# dualScaleBoard_HX711.net
KiCad netlist of a schematic drawn in EAGLE
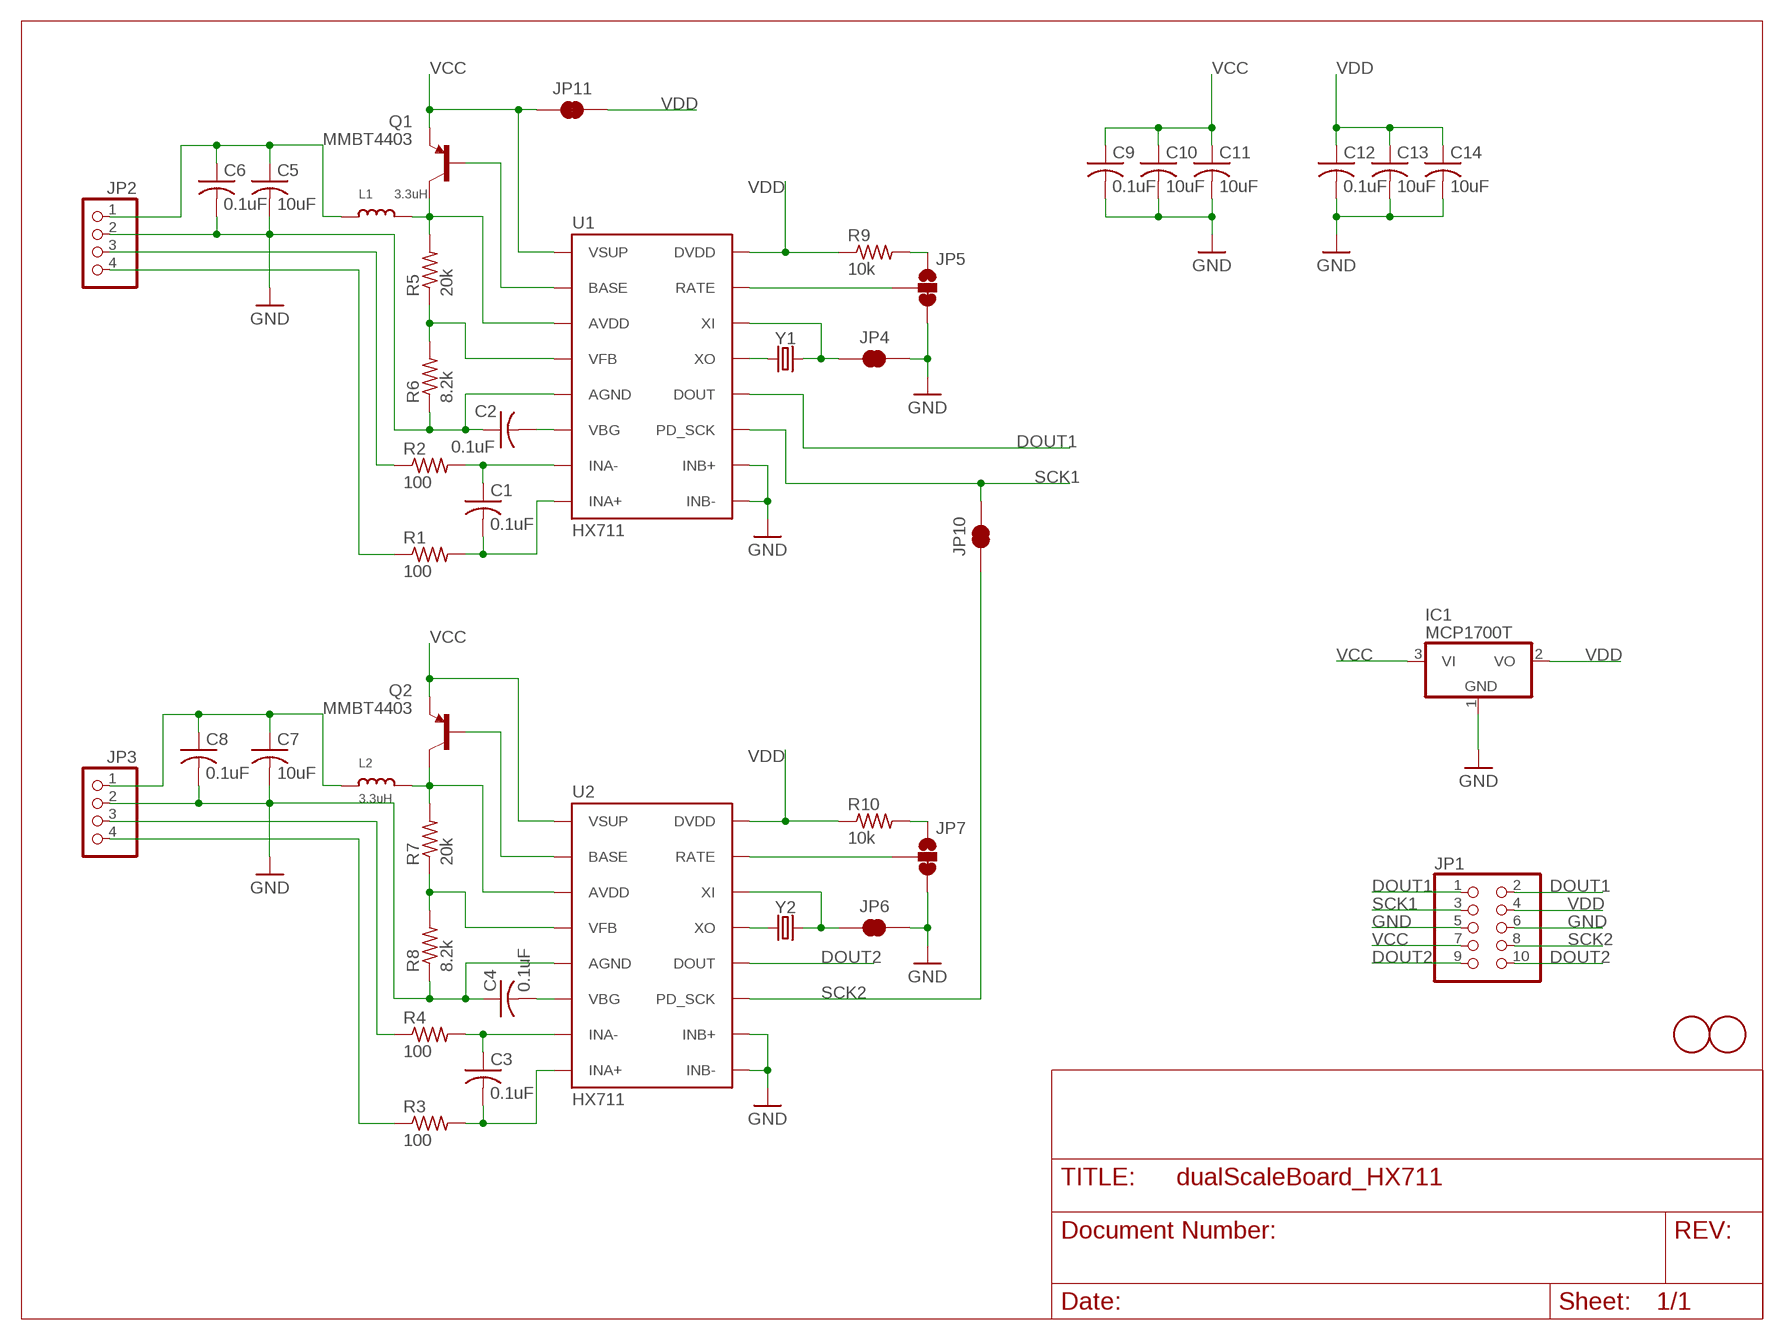
[diagram p0: schematic, sheet 1]

(export (version "E")
  (design (tool "Eeschema 10.0.6"))
  (components
    (comp (ref "C1")
      (value "0.1uF")
      (footprint "eagle-import:C0603")
      (libsource (lib "eagle-import") (part "C-USC0603"))
    )
    (comp (ref "C2")
      (value "0.1uF")
      (footprint "eagle-import:C0603")
      (libsource (lib "eagle-import") (part "C-USC0603"))
    )
    (comp (ref "C3")
      (value "0.1uF")
      (footprint "eagle-import:C0603")
      (libsource (lib "eagle-import") (part "C-USC0603"))
    )
    (comp (ref "C4")
      (value "0.1uF")
      (footprint "eagle-import:C0603")
      (libsource (lib "eagle-import") (part "C-USC0603"))
    )
    (comp (ref "C5")
      (value "10uF")
      (footprint "eagle-import:C0603")
      (libsource (lib "eagle-import") (part "C-USC0603"))
    )
    (comp (ref "C6")
      (value "0.1uF")
      (footprint "eagle-import:C0603")
      (libsource (lib "eagle-import") (part "C-USC0603"))
    )
    (comp (ref "C7")
      (value "10uF")
      (footprint "eagle-import:C0603")
      (libsource (lib "eagle-import") (part "C-USC0603"))
    )
    (comp (ref "C8")
      (value "0.1uF")
      (footprint "eagle-import:C0603")
      (libsource (lib "eagle-import") (part "C-USC0603"))
    )
    (comp (ref "C9")
      (value "0.1uF")
      (footprint "eagle-import:C0603")
      (libsource (lib "eagle-import") (part "C-USC0603"))
    )
    (comp (ref "C10")
      (value "10uF")
      (footprint "eagle-import:C0603")
      (libsource (lib "eagle-import") (part "C-USC0603"))
    )
    (comp (ref "C11")
      (value "10uF")
      (footprint "eagle-import:C0603")
      (libsource (lib "eagle-import") (part "C-USC0603"))
    )
    (comp (ref "C12")
      (value "0.1uF")
      (footprint "eagle-import:C0603")
      (libsource (lib "eagle-import") (part "C-USC0603"))
    )
    (comp (ref "C13")
      (value "10uF")
      (footprint "eagle-import:C0603")
      (libsource (lib "eagle-import") (part "C-USC0603"))
    )
    (comp (ref "C14")
      (value "10uF")
      (footprint "eagle-import:C0603")
      (libsource (lib "eagle-import") (part "C-USC0603"))
    )
    (comp (ref "IC1")
      (value "MCP1700T")
      (footprint "eagle-import:SOT23")
      (libsource (lib "eagle-import") (part "MCP1703CB"))
    )
    (comp (ref "JP1")
      (value "PINHD-2X5")
      (footprint "eagle-import:2X05")
      (libsource (lib "eagle-import") (part "PINHD-2X5"))
    )
    (comp (ref "JP2")
      (value "PINHD-1X4")
      (footprint "eagle-import:1X04")
      (libsource (lib "eagle-import") (part "PINHD-1X4"))
    )
    (comp (ref "JP3")
      (value "PINHD-1X4")
      (footprint "eagle-import:1X04")
      (libsource (lib "eagle-import") (part "PINHD-1X4"))
    )
    (comp (ref "JP4")
      (value "JUMPER-SMT_2_NC_TRACE_SILK")
      (footprint "eagle-import:SMT-JUMPER_2_NC_TRACE_SILK")
      (libsource (lib "eagle-import") (part "JUMPER-SMT_2_NC_TRACE_SILK"))
    )
    (comp (ref "JP5")
      (value "JUMPER-SMT_3_1-NC_TRACE_SILK")
      (footprint "eagle-import:SMT-JUMPER_3_1-NC_TRACE_SILK")
      (libsource (lib "eagle-import") (part "JUMPER-SMT_3_1-NC_TRACE_SILK"))
    )
    (comp (ref "JP6")
      (value "JUMPER-SMT_2_NC_TRACE_SILK")
      (footprint "eagle-import:SMT-JUMPER_2_NC_TRACE_SILK")
      (libsource (lib "eagle-import") (part "JUMPER-SMT_2_NC_TRACE_SILK"))
    )
    (comp (ref "JP7")
      (value "JUMPER-SMT_3_1-NC_TRACE_SILK")
      (footprint "eagle-import:SMT-JUMPER_3_1-NC_TRACE_SILK")
      (libsource (lib "eagle-import") (part "JUMPER-SMT_3_1-NC_TRACE_SILK"))
    )
    (comp (ref "JP10")
      (value "JUMPER-SMT_2_NC_TRACE_SILK")
      (footprint "eagle-import:SMT-JUMPER_2_NC_TRACE_SILK")
      (libsource (lib "eagle-import") (part "JUMPER-SMT_2_NC_TRACE_SILK"))
    )
    (comp (ref "JP11")
      (value "JUMPER-SMT_2_NC_TRACE_SILK")
      (footprint "eagle-import:SMT-JUMPER_2_NC_TRACE_SILK")
      (libsource (lib "eagle-import") (part "JUMPER-SMT_2_NC_TRACE_SILK"))
    )
    (comp (ref "L1")
      (value "3.3uH")
      (footprint "eagle-import:_0603")
      (libsource (lib "eagle-import") (part "INDUCTOR_0603"))
    )
    (comp (ref "L2")
      (value "3.3uH")
      (footprint "eagle-import:_0603")
      (libsource (lib "eagle-import") (part "INDUCTOR_0603"))
    )
    (comp (ref "Q1")
      (value "MMBT4403")
      (footprint "eagle-import:SOT23-3")
      (libsource (lib "eagle-import") (part "TRANSISTOR_PNPMMBT4403"))
    )
    (comp (ref "Q2")
      (value "MMBT4403")
      (footprint "eagle-import:SOT23-3")
      (libsource (lib "eagle-import") (part "TRANSISTOR_PNPMMBT4403"))
    )
    (comp (ref "R1")
      (value "100")
      (footprint "eagle-import:R0402")
      (libsource (lib "eagle-import") (part "R-US_R0402"))
    )
    (comp (ref "R2")
      (value "100")
      (footprint "eagle-import:R0402")
      (libsource (lib "eagle-import") (part "R-US_R0402"))
    )
    (comp (ref "R3")
      (value "100")
      (footprint "eagle-import:R0402")
      (libsource (lib "eagle-import") (part "R-US_R0402"))
    )
    (comp (ref "R4")
      (value "100")
      (footprint "eagle-import:R0402")
      (libsource (lib "eagle-import") (part "R-US_R0402"))
    )
    (comp (ref "R5")
      (value "20k")
      (footprint "eagle-import:R0402")
      (libsource (lib "eagle-import") (part "R-US_R0402"))
    )
    (comp (ref "R6")
      (value "8.2k")
      (footprint "eagle-import:R0402")
      (libsource (lib "eagle-import") (part "R-US_R0402"))
    )
    (comp (ref "R7")
      (value "20k")
      (footprint "eagle-import:R0402")
      (libsource (lib "eagle-import") (part "R-US_R0402"))
    )
    (comp (ref "R8")
      (value "8.2k")
      (footprint "eagle-import:R0402")
      (libsource (lib "eagle-import") (part "R-US_R0402"))
    )
    (comp (ref "R9")
      (value "10k")
      (footprint "eagle-import:R0402")
      (libsource (lib "eagle-import") (part "R-US_R0402"))
    )
    (comp (ref "R10")
      (value "10k")
      (footprint "eagle-import:R0402")
      (libsource (lib "eagle-import") (part "R-US_R0402"))
    )
    (comp (ref "U$1")
      (value "FIDUCIAL")
      (footprint "eagle-import:FIDUCIAL_1MM")
      (libsource (lib "eagle-import") (part "FIDUCIAL"))
    )
    (comp (ref "U$2")
      (value "FIDUCIAL")
      (footprint "eagle-import:FIDUCIAL_1MM")
      (libsource (lib "eagle-import") (part "FIDUCIAL"))
    )
    (comp (ref "U1")
      (value "HX711")
      (footprint "eagle-import:SO16")
      (libsource (lib "eagle-import") (part "HX711"))
    )
    (comp (ref "U2")
      (value "HX711")
      (footprint "eagle-import:SO16")
      (libsource (lib "eagle-import") (part "HX711"))
    )
    (comp (ref "Y1")
      (value "CRYSTALSMD-5X3.2-4PAD")
      (footprint "eagle-import:CRYSTAL-SMD-5X3.2-4PAD")
      (libsource (lib "eagle-import") (part "CRYSTALSMD-5X3.2-4PAD"))
    )
    (comp (ref "Y2")
      (value "CRYSTALSMD-5X3.2-4PAD")
      (footprint "eagle-import:CRYSTAL-SMD-5X3.2-4PAD")
      (libsource (lib "eagle-import") (part "CRYSTALSMD-5X3.2-4PAD"))
    )
  )
  (nets
    (net (code "1") (name "/DOUT1") (class "Default")
      (node (ref "JP1") (pin "1") (pinfunction "1_1") (pintype "passive"))
      (node (ref "JP1") (pin "2") (pinfunction "2_2") (pintype "passive"))
      (node (ref "U1") (pin "12") (pinfunction "DOUT_12") (pintype "bidirectional"))
    )
    (net (code "2") (name "/DOUT2") (class "Default")
      (node (ref "JP1") (pin "10") (pinfunction "10_10") (pintype "passive"))
      (node (ref "JP1") (pin "9") (pinfunction "9_9") (pintype "passive"))
      (node (ref "U2") (pin "12") (pinfunction "DOUT_12") (pintype "bidirectional"))
    )
    (net (code "3") (name "/SCK1") (class "Default")
      (node (ref "JP1") (pin "3") (pinfunction "3_3") (pintype "passive"))
      (node (ref "JP10") (pin "2") (pinfunction "2_2") (pintype "passive"))
      (node (ref "U1") (pin "11") (pinfunction "PD_SCK_11") (pintype "bidirectional"))
    )
    (net (code "4") (name "/SCK2") (class "Default")
      (node (ref "JP1") (pin "8") (pinfunction "8_8") (pintype "passive"))
      (node (ref "JP10") (pin "1") (pinfunction "1_1") (pintype "passive"))
      (node (ref "U2") (pin "11") (pinfunction "PD_SCK_11") (pintype "bidirectional"))
    )
    (net (code "5") (name "/VCC") (class "Default")
      (node (ref "C10") (pin "1") (pinfunction "1_1") (pintype "passive"))
      (node (ref "C11") (pin "1") (pinfunction "1_1") (pintype "passive"))
      (node (ref "C9") (pin "1") (pinfunction "1_1") (pintype "passive"))
      (node (ref "IC1") (pin "3") (pinfunction "VI_3") (pintype "input"))
      (node (ref "JP1") (pin "7") (pinfunction "7_7") (pintype "passive"))
      (node (ref "JP11") (pin "1") (pinfunction "1_1") (pintype "passive"))
      (node (ref "Q1") (pin "2") (pinfunction "E_2") (pintype "passive"))
      (node (ref "Q2") (pin "2") (pinfunction "E_2") (pintype "passive"))
      (node (ref "U1") (pin "1") (pinfunction "VSUP_1") (pintype "bidirectional"))
      (node (ref "U2") (pin "1") (pinfunction "VSUP_1") (pintype "bidirectional"))
    )
    (net (code "6") (name "/VDD") (class "Default")
      (node (ref "C12") (pin "1") (pinfunction "1_1") (pintype "passive"))
      (node (ref "C13") (pin "1") (pinfunction "1_1") (pintype "passive"))
      (node (ref "C14") (pin "1") (pinfunction "1_1") (pintype "passive"))
      (node (ref "IC1") (pin "2") (pinfunction "VO_2") (pintype "passive"))
      (node (ref "JP1") (pin "4") (pinfunction "4_4") (pintype "passive"))
      (node (ref "JP11") (pin "2") (pinfunction "2_2") (pintype "passive"))
      (node (ref "R10") (pin "1") (pinfunction "1_1") (pintype "passive"))
      (node (ref "R9") (pin "1") (pinfunction "1_1") (pintype "passive"))
      (node (ref "U1") (pin "16") (pinfunction "DVDD_16") (pintype "bidirectional"))
      (node (ref "U2") (pin "16") (pinfunction "DVDD_16") (pintype "bidirectional"))
    )
    (net (code "7") (name "GND") (class "Default")
      (node (ref "C10") (pin "2") (pinfunction "2_2") (pintype "passive"))
      (node (ref "C11") (pin "2") (pinfunction "2_2") (pintype "passive"))
      (node (ref "C12") (pin "2") (pinfunction "2_2") (pintype "passive"))
      (node (ref "C13") (pin "2") (pinfunction "2_2") (pintype "passive"))
      (node (ref "C14") (pin "2") (pinfunction "2_2") (pintype "passive"))
      (node (ref "C2") (pin "1") (pinfunction "1_1") (pintype "passive"))
      (node (ref "C4") (pin "1") (pinfunction "1_1") (pintype "passive"))
      (node (ref "C5") (pin "2") (pinfunction "2_2") (pintype "passive"))
      (node (ref "C6") (pin "2") (pinfunction "2_2") (pintype "passive"))
      (node (ref "C7") (pin "2") (pinfunction "2_2") (pintype "passive"))
      (node (ref "C8") (pin "2") (pinfunction "2_2") (pintype "passive"))
      (node (ref "C9") (pin "2") (pinfunction "2_2") (pintype "passive"))
      (node (ref "IC1") (pin "1") (pinfunction "GND_1") (pintype "passive"))
      (node (ref "JP1") (pin "5") (pinfunction "5_5") (pintype "passive"))
      (node (ref "JP1") (pin "6") (pinfunction "6_6") (pintype "passive"))
      (node (ref "JP2") (pin "2") (pinfunction "2_2") (pintype "passive"))
      (node (ref "JP3") (pin "2") (pinfunction "2_2") (pintype "passive"))
      (node (ref "JP4") (pin "2") (pinfunction "2_2") (pintype "passive"))
      (node (ref "JP5") (pin "3") (pinfunction "3_3") (pintype "passive"))
      (node (ref "JP6") (pin "2") (pinfunction "2_2") (pintype "passive"))
      (node (ref "JP7") (pin "3") (pinfunction "3_3") (pintype "passive"))
      (node (ref "R6") (pin "1") (pinfunction "1_1") (pintype "passive"))
      (node (ref "R8") (pin "1") (pinfunction "1_1") (pintype "passive"))
      (node (ref "U1") (pin "10") (pinfunction "INB+_10") (pintype "bidirectional"))
      (node (ref "U1") (pin "5") (pinfunction "AGND_5") (pintype "bidirectional"))
      (node (ref "U1") (pin "9") (pinfunction "INB-_9") (pintype "bidirectional"))
      (node (ref "U2") (pin "10") (pinfunction "INB+_10") (pintype "bidirectional"))
      (node (ref "U2") (pin "5") (pinfunction "AGND_5") (pintype "bidirectional"))
      (node (ref "U2") (pin "9") (pinfunction "INB-_9") (pintype "bidirectional"))
    )
    (net (code "8") (name "Net-(C5-Pad1)") (class "Default")
      (node (ref "C5") (pin "1") (pinfunction "1_1") (pintype "passive"))
      (node (ref "C6") (pin "1") (pinfunction "1_1") (pintype "passive"))
      (node (ref "JP2") (pin "1") (pinfunction "1_1") (pintype "passive"))
      (node (ref "L1") (pin "1") (pinfunction "1_1") (pintype "passive"))
    )
    (net (code "9") (name "Net-(C7-Pad1)") (class "Default")
      (node (ref "C7") (pin "1") (pinfunction "1_1") (pintype "passive"))
      (node (ref "C8") (pin "1") (pinfunction "1_1") (pintype "passive"))
      (node (ref "JP3") (pin "1") (pinfunction "1_1") (pintype "passive"))
      (node (ref "L2") (pin "1") (pinfunction "1_1") (pintype "passive"))
    )
    (net (code "10") (name "Net-(JP2-Pad3)") (class "Default")
      (node (ref "JP2") (pin "3") (pinfunction "3_3") (pintype "passive"))
      (node (ref "R2") (pin "1") (pinfunction "1_1") (pintype "passive"))
    )
    (net (code "11") (name "Net-(JP2-Pad4)") (class "Default")
      (node (ref "JP2") (pin "4") (pinfunction "4_4") (pintype "passive"))
      (node (ref "R1") (pin "1") (pinfunction "1_1") (pintype "passive"))
    )
    (net (code "12") (name "Net-(JP3-Pad3)") (class "Default")
      (node (ref "JP3") (pin "3") (pinfunction "3_3") (pintype "passive"))
      (node (ref "R4") (pin "1") (pinfunction "1_1") (pintype "passive"))
    )
    (net (code "13") (name "Net-(JP3-Pad4)") (class "Default")
      (node (ref "JP3") (pin "4") (pinfunction "4_4") (pintype "passive"))
      (node (ref "R3") (pin "1") (pinfunction "1_1") (pintype "passive"))
    )
    (net (code "14") (name "Net-(JP5-Pad1)") (class "Default")
      (node (ref "JP5") (pin "1") (pinfunction "1_1") (pintype "passive"))
      (node (ref "R9") (pin "2") (pinfunction "2_2") (pintype "passive"))
    )
    (net (code "15") (name "Net-(JP7-Pad1)") (class "Default")
      (node (ref "JP7") (pin "1") (pinfunction "1_1") (pintype "passive"))
      (node (ref "R10") (pin "2") (pinfunction "2_2") (pintype "passive"))
    )
    (net (code "16") (name "Net-(Q1-B)") (class "Default")
      (node (ref "Q1") (pin "1") (pinfunction "B_1") (pintype "passive"))
      (node (ref "U1") (pin "2") (pinfunction "BASE_2") (pintype "bidirectional"))
    )
    (net (code "17") (name "Net-(Q1-C)") (class "Default")
      (node (ref "L1") (pin "2") (pinfunction "2_2") (pintype "passive"))
      (node (ref "Q1") (pin "3") (pinfunction "C_3") (pintype "passive"))
      (node (ref "R5") (pin "2") (pinfunction "2_2") (pintype "passive"))
      (node (ref "U1") (pin "3") (pinfunction "AVDD_3") (pintype "bidirectional"))
    )
    (net (code "18") (name "Net-(Q2-B)") (class "Default")
      (node (ref "Q2") (pin "1") (pinfunction "B_1") (pintype "passive"))
      (node (ref "U2") (pin "2") (pinfunction "BASE_2") (pintype "bidirectional"))
    )
    (net (code "19") (name "Net-(Q2-C)") (class "Default")
      (node (ref "L2") (pin "2") (pinfunction "2_2") (pintype "passive"))
      (node (ref "Q2") (pin "3") (pinfunction "C_3") (pintype "passive"))
      (node (ref "R7") (pin "2") (pinfunction "2_2") (pintype "passive"))
      (node (ref "U2") (pin "3") (pinfunction "AVDD_3") (pintype "bidirectional"))
    )
    (net (code "20") (name "Net-(U1-INA+)") (class "Default")
      (node (ref "C1") (pin "2") (pinfunction "2_2") (pintype "passive"))
      (node (ref "R1") (pin "2") (pinfunction "2_2") (pintype "passive"))
      (node (ref "U1") (pin "8") (pinfunction "INA+_8") (pintype "bidirectional"))
    )
    (net (code "21") (name "Net-(U1-INA-)") (class "Default")
      (node (ref "C1") (pin "1") (pinfunction "1_1") (pintype "passive"))
      (node (ref "R2") (pin "2") (pinfunction "2_2") (pintype "passive"))
      (node (ref "U1") (pin "7") (pinfunction "INA-_7") (pintype "bidirectional"))
    )
    (net (code "22") (name "Net-(U1-RATE)") (class "Default")
      (node (ref "JP5") (pin "2") (pinfunction "2_2") (pintype "passive"))
      (node (ref "U1") (pin "15") (pinfunction "RATE_15") (pintype "bidirectional"))
    )
    (net (code "23") (name "Net-(U1-VBG)") (class "Default")
      (node (ref "C2") (pin "2") (pinfunction "2_2") (pintype "passive"))
      (node (ref "U1") (pin "6") (pinfunction "VBG_6") (pintype "bidirectional"))
    )
    (net (code "24") (name "Net-(U1-VFB)") (class "Default")
      (node (ref "R5") (pin "1") (pinfunction "1_1") (pintype "passive"))
      (node (ref "R6") (pin "2") (pinfunction "2_2") (pintype "passive"))
      (node (ref "U1") (pin "4") (pinfunction "VFB_4") (pintype "bidirectional"))
    )
    (net (code "25") (name "Net-(U1-XI)") (class "Default")
      (node (ref "JP4") (pin "1") (pinfunction "1_1") (pintype "passive"))
      (node (ref "U1") (pin "14") (pinfunction "XI_14") (pintype "bidirectional"))
      (node (ref "Y1") (pin "3") (pinfunction "2_3") (pintype "passive"))
    )
    (net (code "26") (name "Net-(U1-XO)") (class "Default")
      (node (ref "U1") (pin "13") (pinfunction "XO_13") (pintype "bidirectional"))
      (node (ref "Y1") (pin "1") (pinfunction "1_1") (pintype "passive"))
    )
    (net (code "27") (name "Net-(U2-INA+)") (class "Default")
      (node (ref "C3") (pin "2") (pinfunction "2_2") (pintype "passive"))
      (node (ref "R3") (pin "2") (pinfunction "2_2") (pintype "passive"))
      (node (ref "U2") (pin "8") (pinfunction "INA+_8") (pintype "bidirectional"))
    )
    (net (code "28") (name "Net-(U2-INA-)") (class "Default")
      (node (ref "C3") (pin "1") (pinfunction "1_1") (pintype "passive"))
      (node (ref "R4") (pin "2") (pinfunction "2_2") (pintype "passive"))
      (node (ref "U2") (pin "7") (pinfunction "INA-_7") (pintype "bidirectional"))
    )
    (net (code "29") (name "Net-(U2-RATE)") (class "Default")
      (node (ref "JP7") (pin "2") (pinfunction "2_2") (pintype "passive"))
      (node (ref "U2") (pin "15") (pinfunction "RATE_15") (pintype "bidirectional"))
    )
    (net (code "30") (name "Net-(U2-VBG)") (class "Default")
      (node (ref "C4") (pin "2") (pinfunction "2_2") (pintype "passive"))
      (node (ref "U2") (pin "6") (pinfunction "VBG_6") (pintype "bidirectional"))
    )
    (net (code "31") (name "Net-(U2-VFB)") (class "Default")
      (node (ref "R7") (pin "1") (pinfunction "1_1") (pintype "passive"))
      (node (ref "R8") (pin "2") (pinfunction "2_2") (pintype "passive"))
      (node (ref "U2") (pin "4") (pinfunction "VFB_4") (pintype "bidirectional"))
    )
    (net (code "32") (name "Net-(U2-XI)") (class "Default")
      (node (ref "JP6") (pin "1") (pinfunction "1_1") (pintype "passive"))
      (node (ref "U2") (pin "14") (pinfunction "XI_14") (pintype "bidirectional"))
      (node (ref "Y2") (pin "3") (pinfunction "2_3") (pintype "passive"))
    )
    (net (code "33") (name "Net-(U2-XO)") (class "Default")
      (node (ref "U2") (pin "13") (pinfunction "XO_13") (pintype "bidirectional"))
      (node (ref "Y2") (pin "1") (pinfunction "1_1") (pintype "passive"))
    )
  )
)
